# SEQ.net
KiCad netlist of a schematic drawn in EAGLE
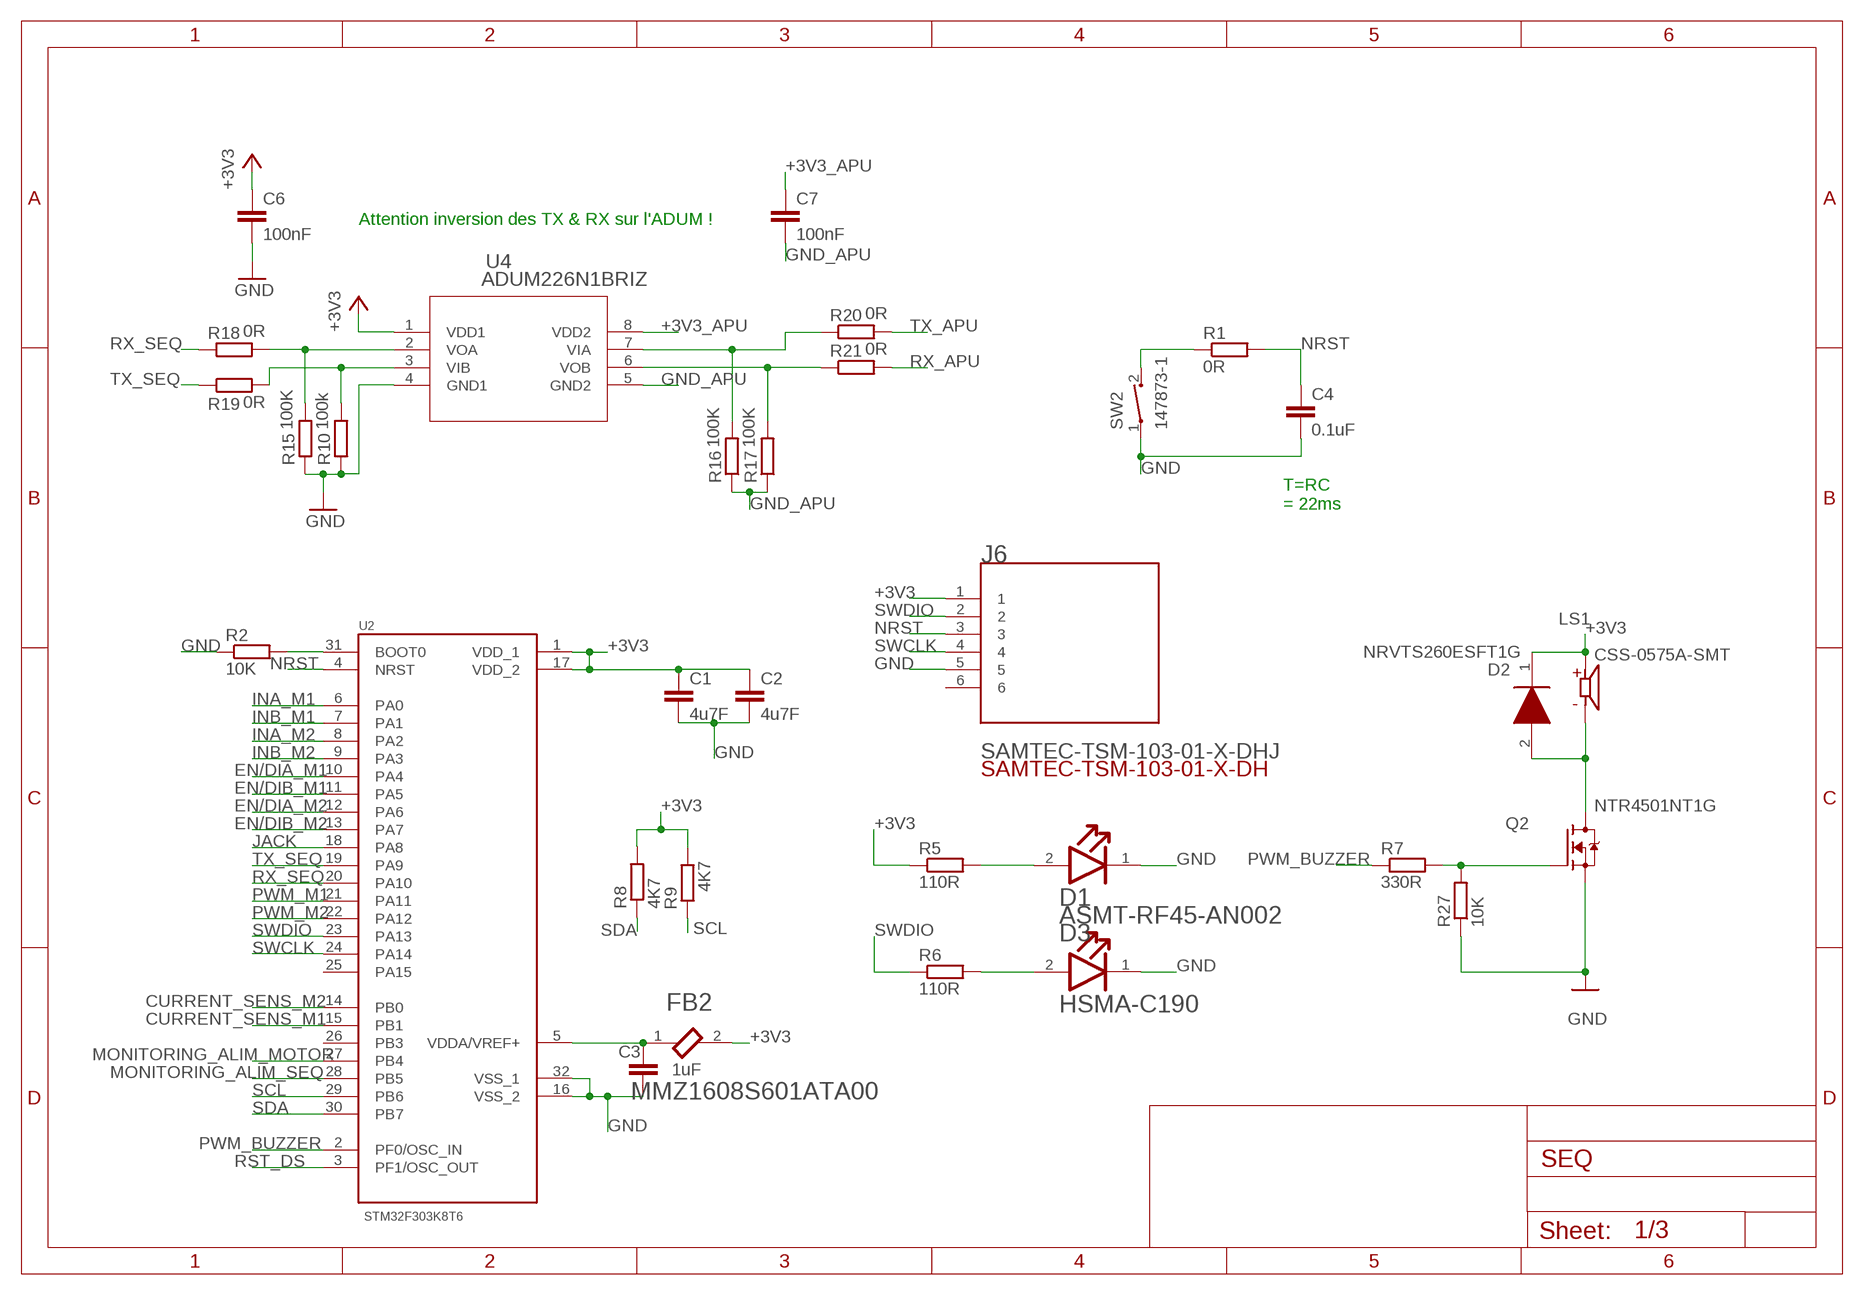
[diagram p0: schematic, sheet 1]
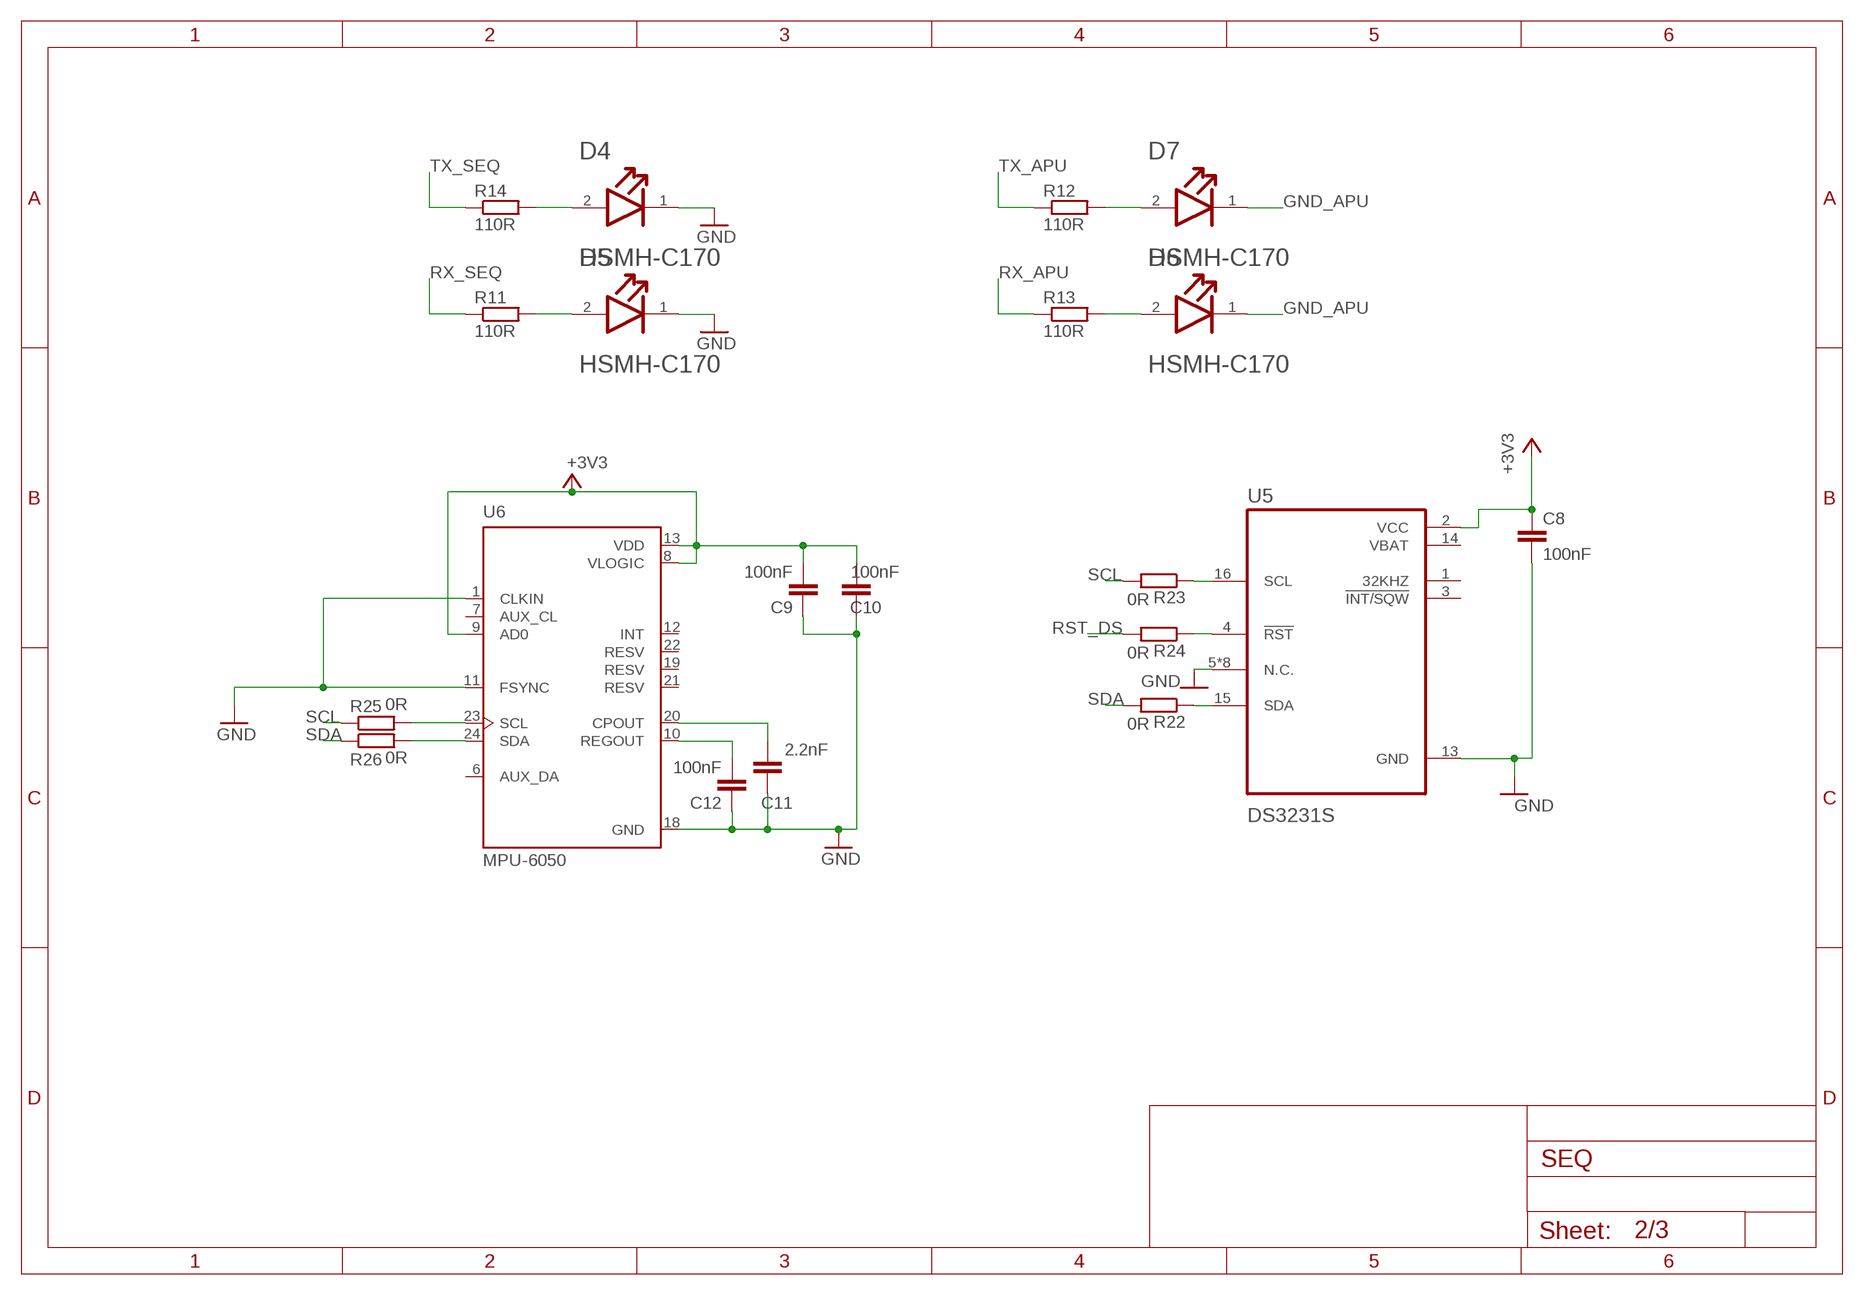
[diagram p1: schematic, sheet 2]
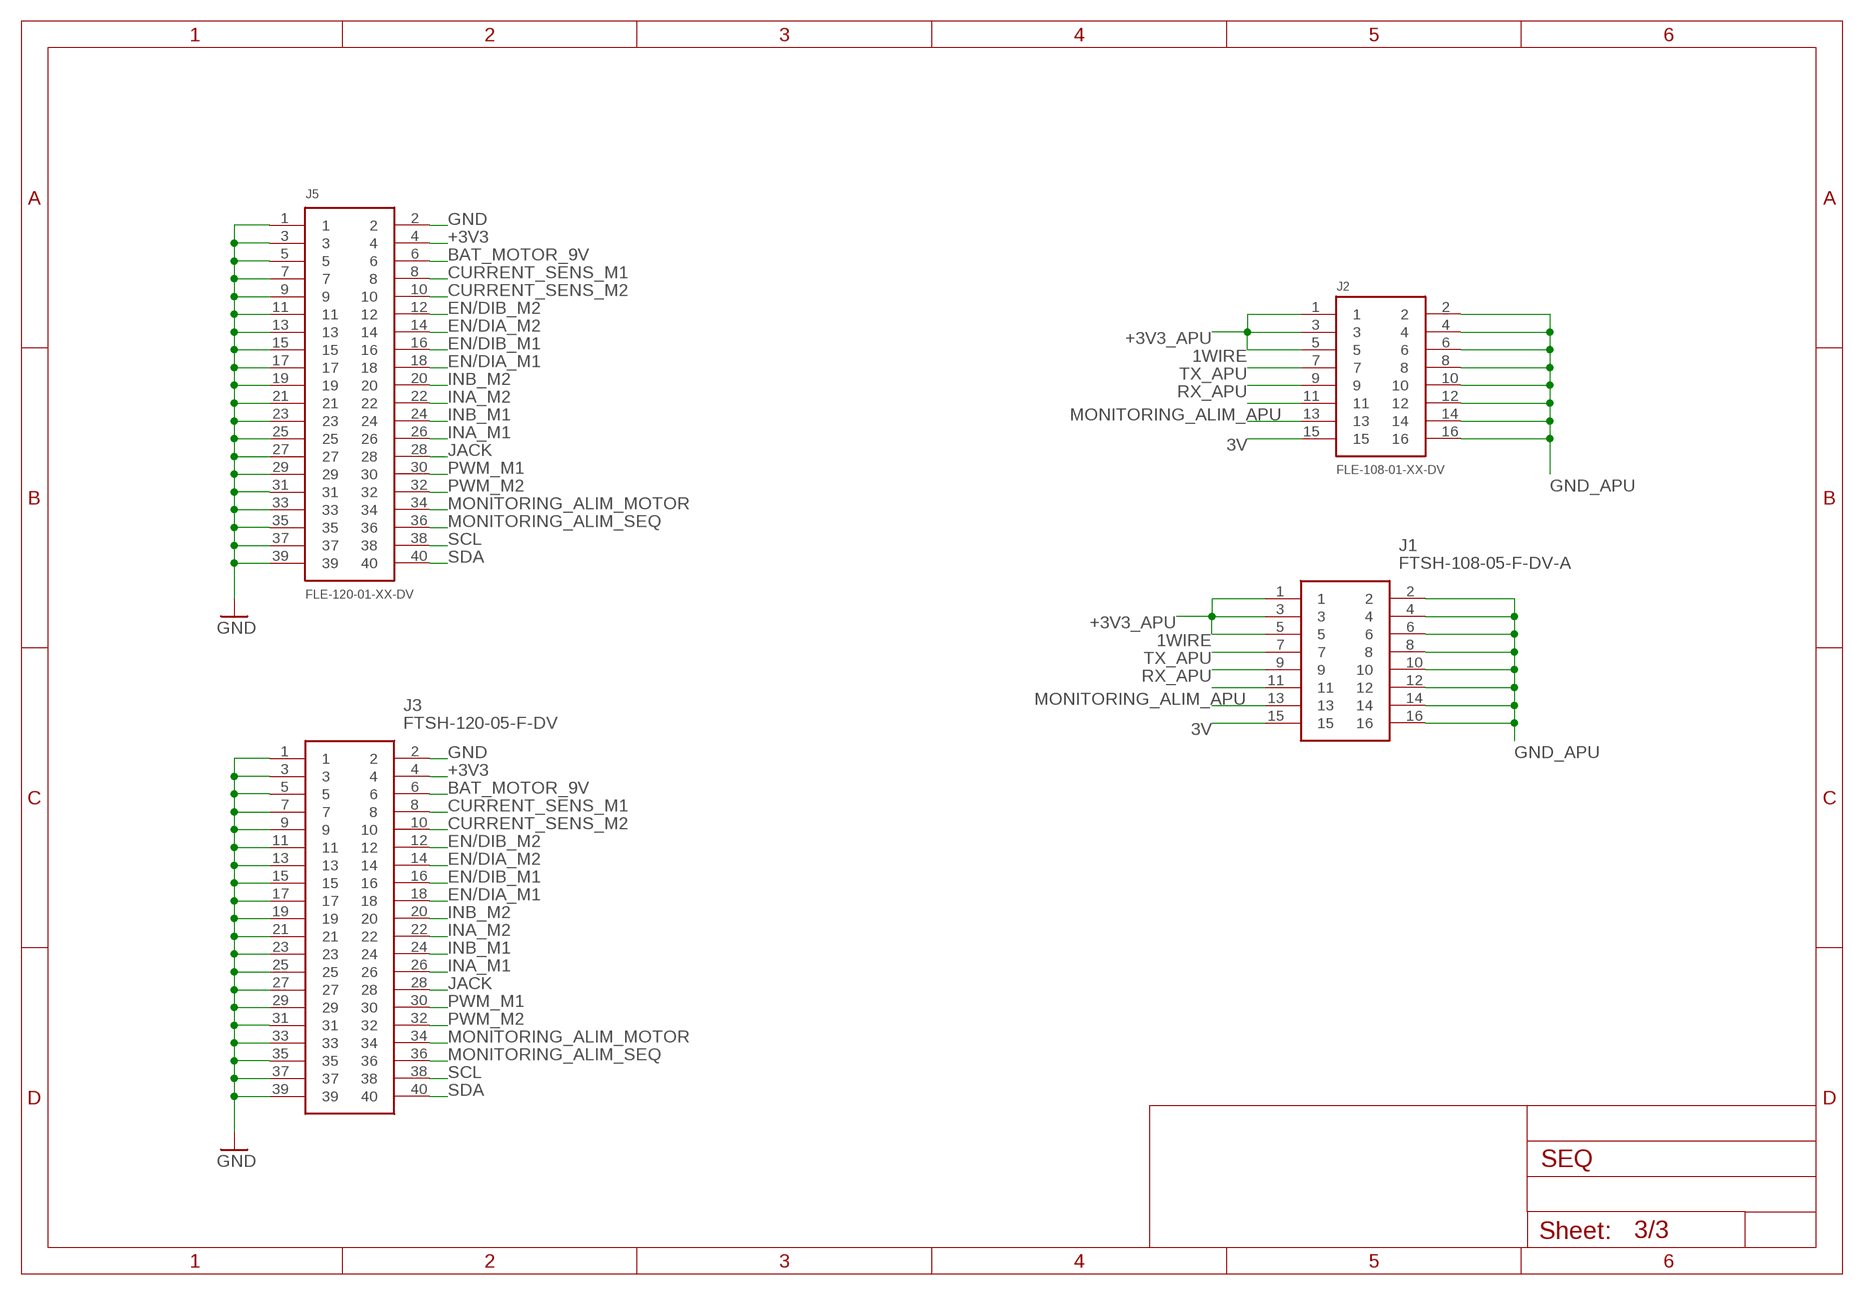
[diagram p2: schematic, sheet 3]

(export (version "E")
  (design (tool "Eeschema 10.0.6"))
  (components
    (comp (ref "C1")
      (value "4u7F")
      (footprint "eagle-import:C0805K")
      (libsource (lib "eagle-import") (part "C-EUC0805K"))
    )
    (comp (ref "C2")
      (value "4u7F")
      (footprint "eagle-import:C0805K")
      (libsource (lib "eagle-import") (part "C-EUC0805K"))
    )
    (comp (ref "C3")
      (value "1uF")
      (footprint "eagle-import:C0805K")
      (libsource (lib "eagle-import") (part "C-EUC0805K"))
    )
    (comp (ref "C4")
      (value "0.1uF")
      (footprint "eagle-import:C0805K")
      (libsource (lib "eagle-import") (part "C-EUC0805K"))
    )
    (comp (ref "C6")
      (value "100nF")
      (footprint "eagle-import:C0805")
      (libsource (lib "eagle-import") (part "C-EUC0805"))
    )
    (comp (ref "C7")
      (value "100nF")
      (footprint "eagle-import:C0805")
      (libsource (lib "eagle-import") (part "C-EUC0805"))
    )
    (comp (ref "D1")
      (value "BROADCOM_ASMT-RF45-AN002BROADCOM_ASMT-RF45-AN002_0_0")
      (footprint "eagle-import:BROADCOM_ASMT-RF45-AN002_0")
      (fields
        (field (name "DIGIKEY_PART_NUMBER") "516-2522-1-ND")
        (field (name "MF") "Broadcom")
        (field (name "MOUSER_PART_NUMBER") "630-ASMT-RF45-AN002")
      )
      (libsource (lib "eagle-import") (part "BROADCOM_ASMT-RF45-AN002BROADCOM_ASMT-RF45-AN002_0_0"))
    )
    (comp (ref "D2")
      (value "NRVTS260ESFT1G")
      (footprint "eagle-import:SODFL3616X98N")
      (fields (field (name "MOUSER_PART_NUMBER") "863-NRVTS260ESFT1G"))
      (libsource (lib "eagle-import") (part "NRVTS260ESFT1G"))
    )
    (comp (ref "D3")
      (value "BROADCOM_HSMA-C190BROADCOM_HSMA-C190_0_0")
      (footprint "eagle-import:BROADCOM_HSMA-C190_0")
      (fields
        (field (name "DIGIKEY_PART_NUMBER") "516-1423-1-ND")
        (field (name "MF") "Broadcom")
        (field (name "MOUSER_PART_NUMBER") "630-HSMA-C190")
      )
      (libsource (lib "eagle-import") (part "BROADCOM_HSMA-C190BROADCOM_HSMA-C190_0_0"))
    )
    (comp (ref "FB2")
      (value "TDK_MMZ1608S601ATA00TDK_MMZ1608S601ATA00_0_0")
      (footprint "eagle-import:TDK_MMZ1608S601ATA00_0")
      (fields
        (field (name "MF") "TDK")
        (field (name "MPN") "MMZ1608S601ATA00")
        (field (name "TOLERANCE") "25%")
      )
      (libsource (lib "eagle-import") (part "TDK_MMZ1608S601ATA00TDK_MMZ1608S601ATA00_0_0"))
    )
    (comp (ref "J6")
      (value "SAMTEC-TSM-103-01-X-DHJ")
      (footprint "eagle-import:SAMTEC-TSM-103-01-X-DH")
      (fields (field (name "MF") "Samtec Inc.") (field (name "MP") "TSM-103-01-F-DH"))
      (libsource (lib "eagle-import") (part "SAMTEC-TSM-103-01-X-DHJ"))
    )
    (comp (ref "LS1")
      (value "CSS-0575A-SMT")
      (footprint "eagle-import:CUI_CSS-0575A-SMT")
      (fields (field (name "MF") "CUI"))
      (libsource (lib "eagle-import") (part "CSS-0575A-SMT"))
    )
    (comp (ref "Q2")
      (value "NTR4501NT1G")
      (footprint "eagle-import:SOT95P237X111-3N")
      (fields (field (name "MF") "ON Semiconductor"))
      (libsource (lib "eagle-import") (part "NTR4501NT1G"))
    )
    (comp (ref "R1")
      (value "0R")
      (footprint "eagle-import:R0603")
      (libsource (lib "eagle-import") (part "R-EU_R0603"))
    )
    (comp (ref "R2")
      (value "10K")
      (footprint "eagle-import:R0603")
      (libsource (lib "eagle-import") (part "R-EU_R0603"))
    )
    (comp (ref "R5")
      (value "110R")
      (footprint "eagle-import:R0603")
      (libsource (lib "eagle-import") (part "R-EU_R0603"))
    )
    (comp (ref "R6")
      (value "110R")
      (footprint "eagle-import:R0603")
      (libsource (lib "eagle-import") (part "R-EU_R0603"))
    )
    (comp (ref "R7")
      (value "330R")
      (footprint "eagle-import:R0603")
      (libsource (lib "eagle-import") (part "R-EU_R0603"))
    )
    (comp (ref "R8")
      (value "4K7")
      (footprint "eagle-import:R0603")
      (libsource (lib "eagle-import") (part "R-EU_R0603"))
    )
    (comp (ref "R9")
      (value "4K7")
      (footprint "eagle-import:R0603")
      (libsource (lib "eagle-import") (part "R-EU_R0603"))
    )
    (comp (ref "R10")
      (value "100k")
      (footprint "eagle-import:R0603")
      (libsource (lib "eagle-import") (part "R-EU_R0603"))
    )
    (comp (ref "R15")
      (value "100K")
      (footprint "eagle-import:R0603")
      (libsource (lib "eagle-import") (part "R-EU_R0603"))
    )
    (comp (ref "R16")
      (value "100K")
      (footprint "eagle-import:R0603")
      (libsource (lib "eagle-import") (part "R-EU_R0603"))
    )
    (comp (ref "R17")
      (value "100K")
      (footprint "eagle-import:R0603")
      (libsource (lib "eagle-import") (part "R-EU_R0603"))
    )
    (comp (ref "R18")
      (value "0R")
      (footprint "eagle-import:R0603")
      (libsource (lib "eagle-import") (part "R-EU_R0603"))
    )
    (comp (ref "R19")
      (value "0R")
      (footprint "eagle-import:R0603")
      (libsource (lib "eagle-import") (part "R-EU_R0603"))
    )
    (comp (ref "R20")
      (value "0R")
      (footprint "eagle-import:R0603")
      (libsource (lib "eagle-import") (part "R-EU_R0603"))
    )
    (comp (ref "R21")
      (value "0R")
      (footprint "eagle-import:R0603")
      (libsource (lib "eagle-import") (part "R-EU_R0603"))
    )
    (comp (ref "R27")
      (value "10K")
      (footprint "eagle-import:R0603")
      (libsource (lib "eagle-import") (part "R-EU_R0603"))
    )
    (comp (ref "SW2")
      (value "147873-1")
      (footprint "eagle-import:SW_147873-1")
      (fields (field (name "MF") "TE Connectivity"))
      (libsource (lib "eagle-import") (part "147873-1"))
    )
    (comp (ref "U2")
      (value "STM32F303K8T6")
      (footprint "eagle-import:QFP80P900X900X160-32N")
      (fields (field (name "MANUFACTURER") "ST microelectronics"))
      (libsource (lib "eagle-import") (part "STM32F303K8T6"))
    )
    (comp (ref "U4")
      (value "ADUM226N1BRIZ")
      (footprint "eagle-import:RI_8_1_ADI")
      (libsource (lib "eagle-import") (part "ADUM226N1BRIZ"))
    )
    (comp (ref "J1")
      (value "FTSH-108-05-F-DV-A")
      (footprint "eagle-import:FTSH-108-XX-YYY-DV-A")
      (fields (field (name "MOUSER_PART_NUMBER") "200-FTSH10805FDVA"))
      (libsource (lib "eagle-import") (part "FTSH-108-05-F-DV-A"))
    )
    (comp (ref "J2")
      (value "FLE-108-01-XX-DV")
      (footprint "eagle-import:FLE-108-01-XX-DV")
      (fields (field (name "MF") "Samtec") (field (name "MP") "FLE-108-01-G-DV"))
      (libsource (lib "eagle-import") (part "FLE-108-01-XX-DV"))
    )
    (comp (ref "J3")
      (value "FTSH-120-05-F-DV")
      (footprint "eagle-import:FTSH-120-XX-YYY-DV")
      (libsource (lib "eagle-import") (part "FTSH-120-05-F-DV"))
    )
    (comp (ref "J5")
      (value "FLE-120-01-XX-DV")
      (footprint "eagle-import:FLE-120-01-XX-DV")
      (fields (field (name "MF") "Samtec") (field (name "MP") "FLE-120-01-G-DV"))
      (libsource (lib "eagle-import") (part "FLE-120-01-XX-DV"))
    )
    (comp (ref "C8")
      (value "100nF")
      (footprint "eagle-import:C0805")
      (libsource (lib "eagle-import") (part "C-EUC0805"))
    )
    (comp (ref "C9")
      (value "100nF")
      (footprint "eagle-import:C0805")
      (libsource (lib "eagle-import") (part "C-EUC0805"))
    )
    (comp (ref "C10")
      (value "100nF")
      (footprint "eagle-import:C0805")
      (libsource (lib "eagle-import") (part "C-EUC0805"))
    )
    (comp (ref "C11")
      (value "2.2nF")
      (footprint "eagle-import:C0805")
      (libsource (lib "eagle-import") (part "C-EUC0805"))
    )
    (comp (ref "C12")
      (value "100nF")
      (footprint "eagle-import:C0805")
      (libsource (lib "eagle-import") (part "C-EUC0805"))
    )
    (comp (ref "D4")
      (value "BROADCOM_HSMH-C170BROADCOM_HSMH-C170_0_0")
      (footprint "eagle-import:BROADCOM_HSMH-C170_0")
      (fields
        (field (name "DIGIKEY_PART_NUMBER") "516-1427-1-ND")
        (field (name "MF") "Broadcom")
        (field (name "MOUSER_PART_NUMBER") "630-HSMH-C170")
      )
      (libsource (lib "eagle-import") (part "BROADCOM_HSMH-C170BROADCOM_HSMH-C170_0_0"))
    )
    (comp (ref "D5")
      (value "BROADCOM_HSMH-C170BROADCOM_HSMH-C170_0_0")
      (footprint "eagle-import:BROADCOM_HSMH-C170_0")
      (fields
        (field (name "DIGIKEY_PART_NUMBER") "516-1427-1-ND")
        (field (name "MF") "Broadcom")
        (field (name "MOUSER_PART_NUMBER") "630-HSMH-C170")
      )
      (libsource (lib "eagle-import") (part "BROADCOM_HSMH-C170BROADCOM_HSMH-C170_0_0"))
    )
    (comp (ref "D6")
      (value "BROADCOM_HSMH-C170BROADCOM_HSMH-C170_0_0")
      (footprint "eagle-import:BROADCOM_HSMH-C170_0")
      (fields
        (field (name "DIGIKEY_PART_NUMBER") "516-1427-1-ND")
        (field (name "MF") "Broadcom")
        (field (name "MOUSER_PART_NUMBER") "630-HSMH-C170")
      )
      (libsource (lib "eagle-import") (part "BROADCOM_HSMH-C170BROADCOM_HSMH-C170_0_0"))
    )
    (comp (ref "D7")
      (value "BROADCOM_HSMH-C170BROADCOM_HSMH-C170_0_0")
      (footprint "eagle-import:BROADCOM_HSMH-C170_0")
      (fields
        (field (name "DIGIKEY_PART_NUMBER") "516-1427-1-ND")
        (field (name "MF") "Broadcom")
        (field (name "MOUSER_PART_NUMBER") "630-HSMH-C170")
      )
      (libsource (lib "eagle-import") (part "BROADCOM_HSMH-C170BROADCOM_HSMH-C170_0_0"))
    )
    (comp (ref "R11")
      (value "110R")
      (footprint "eagle-import:R0603")
      (libsource (lib "eagle-import") (part "R-EU_R0603"))
    )
    (comp (ref "R12")
      (value "110R")
      (footprint "eagle-import:R0603")
      (libsource (lib "eagle-import") (part "R-EU_R0603"))
    )
    (comp (ref "R13")
      (value "110R")
      (footprint "eagle-import:R0603")
      (libsource (lib "eagle-import") (part "R-EU_R0603"))
    )
    (comp (ref "R14")
      (value "110R")
      (footprint "eagle-import:R0603")
      (libsource (lib "eagle-import") (part "R-EU_R0603"))
    )
    (comp (ref "R22")
      (value "0R")
      (footprint "eagle-import:R0603")
      (libsource (lib "eagle-import") (part "R-EU_R0603"))
    )
    (comp (ref "R23")
      (value "0R")
      (footprint "eagle-import:R0603")
      (libsource (lib "eagle-import") (part "R-EU_R0603"))
    )
    (comp (ref "R24")
      (value "0R")
      (footprint "eagle-import:R0603")
      (libsource (lib "eagle-import") (part "R-EU_R0603"))
    )
    (comp (ref "R25")
      (value "0R")
      (footprint "eagle-import:R0603")
      (libsource (lib "eagle-import") (part "R-EU_R0603"))
    )
    (comp (ref "R26")
      (value "0R")
      (footprint "eagle-import:R0603")
      (libsource (lib "eagle-import") (part "R-EU_R0603"))
    )
    (comp (ref "U5")
      (value "DS3231S")
      (footprint "eagle-import:SOIC127P1032X265-16N")
      (fields (field (name "MF") "Maxim Integrated"))
      (libsource (lib "eagle-import") (part "DS3231S"))
    )
    (comp (ref "U6")
      (value "MPU-6050")
      (footprint "eagle-import:QFN50P400X400X95-24N")
      (fields (field (name "MF") "TDK InvenSense"))
      (libsource (lib "eagle-import") (part "MPU-6050"))
    )
  )
  (nets
    (net (code "1") (name "+3V3") (class "Default")
      (node (ref "C1") (pin "1") (pinfunction "1_1") (pintype "passive"))
      (node (ref "C10") (pin "2") (pinfunction "2_2") (pintype "passive"))
      (node (ref "C2") (pin "1") (pinfunction "1_1") (pintype "passive"))
      (node (ref "C6") (pin "1") (pinfunction "1_1") (pintype "passive"))
      (node (ref "C8") (pin "1") (pinfunction "1_1") (pintype "passive"))
      (node (ref "C9") (pin "2") (pinfunction "2_2") (pintype "passive"))
      (node (ref "D2") (pin "1") (pinfunction "K_1") (pintype "bidirectional"))
      (node (ref "FB2") (pin "2") (pinfunction "2_2") (pintype "passive"))
      (node (ref "J3") (pin "4") (pinfunction "4_4") (pintype "bidirectional"))
      (node (ref "J5") (pin "4") (pinfunction "4_4") (pintype "bidirectional"))
      (node (ref "J6") (pin "1") (pinfunction "1_1") (pintype "bidirectional"))
      (node (ref "LS1") (pin "1") (pinfunction "P_1") (pintype "passive"))
      (node (ref "R5") (pin "1") (pinfunction "1_1") (pintype "passive"))
      (node (ref "R8") (pin "2") (pinfunction "2_2") (pintype "passive"))
      (node (ref "R9") (pin "2") (pinfunction "2_2") (pintype "passive"))
      (node (ref "U2") (pin "1") (pinfunction "VDD_1_1") (pintype "power_in"))
      (node (ref "U2") (pin "17") (pinfunction "VDD_2_17") (pintype "power_in"))
      (node (ref "U4") (pin "1") (pinfunction "VDD1_1") (pintype "passive"))
      (node (ref "U5") (pin "2") (pinfunction "VCC_2") (pintype "power_in"))
      (node (ref "U6") (pin "13") (pinfunction "VDD_13") (pintype "power_in"))
      (node (ref "U6") (pin "8") (pinfunction "VLOGIC_8") (pintype "power_in"))
      (node (ref "U6") (pin "9") (pinfunction "AD0_9") (pintype "input"))
    )
    (net (code "2") (name "+3V3_APU") (class "Default")
      (node (ref "C7") (pin "1") (pinfunction "1_1") (pintype "passive"))
      (node (ref "J1") (pin "1") (pinfunction "1_1") (pintype "bidirectional"))
      (node (ref "J1") (pin "3") (pinfunction "3_3") (pintype "bidirectional"))
      (node (ref "J1") (pin "5") (pinfunction "5_5") (pintype "bidirectional"))
      (node (ref "J2") (pin "1") (pinfunction "1_1") (pintype "bidirectional"))
      (node (ref "J2") (pin "3") (pinfunction "3_3") (pintype "bidirectional"))
      (node (ref "J2") (pin "5") (pinfunction "5_5") (pintype "bidirectional"))
      (node (ref "U4") (pin "8") (pinfunction "VDD2_8") (pintype "passive"))
    )
    (net (code "3") (name "1WIRE") (class "Default")
      (node (ref "J1") (pin "7") (pinfunction "7_7") (pintype "bidirectional"))
      (node (ref "J2") (pin "7") (pinfunction "7_7") (pintype "bidirectional"))
    )
    (net (code "4") (name "3V") (class "Default")
      (node (ref "J1") (pin "15") (pinfunction "15_15") (pintype "bidirectional"))
      (node (ref "J2") (pin "15") (pinfunction "15_15") (pintype "bidirectional"))
    )
    (net (code "5") (name "BAT_MOTOR_9V") (class "Default")
      (node (ref "J3") (pin "6") (pinfunction "6_6") (pintype "bidirectional"))
      (node (ref "J5") (pin "6") (pinfunction "6_6") (pintype "bidirectional"))
    )
    (net (code "6") (name "CURRENT_SENS_M1") (class "Default")
      (node (ref "J3") (pin "8") (pinfunction "8_8") (pintype "bidirectional"))
      (node (ref "J5") (pin "8") (pinfunction "8_8") (pintype "bidirectional"))
      (node (ref "U2") (pin "15") (pinfunction "PB1_15") (pintype "bidirectional"))
    )
    (net (code "7") (name "CURRENT_SENS_M2") (class "Default")
      (node (ref "J3") (pin "10") (pinfunction "10_10") (pintype "bidirectional"))
      (node (ref "J5") (pin "10") (pinfunction "10_10") (pintype "bidirectional"))
      (node (ref "U2") (pin "14") (pinfunction "PB0_14") (pintype "bidirectional"))
    )
    (net (code "8") (name "EN{slash}DIA_M1") (class "Default")
      (node (ref "J3") (pin "18") (pinfunction "18_18") (pintype "bidirectional"))
      (node (ref "J5") (pin "18") (pinfunction "18_18") (pintype "bidirectional"))
      (node (ref "U2") (pin "10") (pinfunction "PA4_10") (pintype "bidirectional"))
    )
    (net (code "9") (name "EN{slash}DIA_M2") (class "Default")
      (node (ref "J3") (pin "14") (pinfunction "14_14") (pintype "bidirectional"))
      (node (ref "J5") (pin "14") (pinfunction "14_14") (pintype "bidirectional"))
      (node (ref "U2") (pin "12") (pinfunction "PA6_12") (pintype "bidirectional"))
    )
    (net (code "10") (name "EN{slash}DIB_M1") (class "Default")
      (node (ref "J3") (pin "16") (pinfunction "16_16") (pintype "bidirectional"))
      (node (ref "J5") (pin "16") (pinfunction "16_16") (pintype "bidirectional"))
      (node (ref "U2") (pin "11") (pinfunction "PA5_11") (pintype "bidirectional"))
    )
    (net (code "11") (name "EN{slash}DIB_M2") (class "Default")
      (node (ref "J3") (pin "12") (pinfunction "12_12") (pintype "bidirectional"))
      (node (ref "J5") (pin "12") (pinfunction "12_12") (pintype "bidirectional"))
      (node (ref "U2") (pin "13") (pinfunction "PA7_13") (pintype "bidirectional"))
    )
    (net (code "12") (name "GND") (class "Default")
      (node (ref "C1") (pin "2") (pinfunction "2_2") (pintype "passive"))
      (node (ref "C10") (pin "1") (pinfunction "1_1") (pintype "passive"))
      (node (ref "C11") (pin "1") (pinfunction "1_1") (pintype "passive"))
      (node (ref "C12") (pin "1") (pinfunction "1_1") (pintype "passive"))
      (node (ref "C2") (pin "2") (pinfunction "2_2") (pintype "passive"))
      (node (ref "C3") (pin "2") (pinfunction "2_2") (pintype "passive"))
      (node (ref "C4") (pin "2") (pinfunction "2_2") (pintype "passive"))
      (node (ref "C6") (pin "2") (pinfunction "2_2") (pintype "passive"))
      (node (ref "C8") (pin "2") (pinfunction "2_2") (pintype "passive"))
      (node (ref "C9") (pin "1") (pinfunction "1_1") (pintype "passive"))
      (node (ref "D1") (pin "1") (pinfunction "CATHODE_1") (pintype "passive"))
      (node (ref "D3") (pin "1") (pinfunction "CATHODE_1") (pintype "passive"))
      (node (ref "D4") (pin "1") (pinfunction "CATHODE_1") (pintype "passive"))
      (node (ref "D5") (pin "1") (pinfunction "CATHODE_1") (pintype "passive"))
      (node (ref "J3") (pin "1") (pinfunction "1_1") (pintype "bidirectional"))
      (node (ref "J3") (pin "11") (pinfunction "11_11") (pintype "bidirectional"))
      (node (ref "J3") (pin "13") (pinfunction "13_13") (pintype "bidirectional"))
      (node (ref "J3") (pin "15") (pinfunction "15_15") (pintype "bidirectional"))
      (node (ref "J3") (pin "17") (pinfunction "17_17") (pintype "bidirectional"))
      (node (ref "J3") (pin "19") (pinfunction "19_19") (pintype "bidirectional"))
      (node (ref "J3") (pin "2") (pinfunction "2_2") (pintype "bidirectional"))
      (node (ref "J3") (pin "21") (pinfunction "21_21") (pintype "bidirectional"))
      (node (ref "J3") (pin "23") (pinfunction "23_23") (pintype "bidirectional"))
      (node (ref "J3") (pin "25") (pinfunction "25_25") (pintype "bidirectional"))
      (node (ref "J3") (pin "27") (pinfunction "27_27") (pintype "bidirectional"))
      (node (ref "J3") (pin "29") (pinfunction "29_29") (pintype "bidirectional"))
      (node (ref "J3") (pin "3") (pinfunction "3_3") (pintype "bidirectional"))
      (node (ref "J3") (pin "31") (pinfunction "31_31") (pintype "bidirectional"))
      (node (ref "J3") (pin "33") (pinfunction "33_33") (pintype "bidirectional"))
      (node (ref "J3") (pin "35") (pinfunction "35_35") (pintype "bidirectional"))
      (node (ref "J3") (pin "37") (pinfunction "37_37") (pintype "bidirectional"))
      (node (ref "J3") (pin "39") (pinfunction "39_39") (pintype "bidirectional"))
      (node (ref "J3") (pin "5") (pinfunction "5_5") (pintype "bidirectional"))
      (node (ref "J3") (pin "7") (pinfunction "7_7") (pintype "bidirectional"))
      (node (ref "J3") (pin "9") (pinfunction "9_9") (pintype "bidirectional"))
      (node (ref "J5") (pin "1") (pinfunction "1_1") (pintype "bidirectional"))
      (node (ref "J5") (pin "11") (pinfunction "11_11") (pintype "bidirectional"))
      (node (ref "J5") (pin "13") (pinfunction "13_13") (pintype "bidirectional"))
      (node (ref "J5") (pin "15") (pinfunction "15_15") (pintype "bidirectional"))
      (node (ref "J5") (pin "17") (pinfunction "17_17") (pintype "bidirectional"))
      (node (ref "J5") (pin "19") (pinfunction "19_19") (pintype "bidirectional"))
      (node (ref "J5") (pin "2") (pinfunction "2_2") (pintype "bidirectional"))
      (node (ref "J5") (pin "21") (pinfunction "21_21") (pintype "bidirectional"))
      (node (ref "J5") (pin "23") (pinfunction "23_23") (pintype "bidirectional"))
      (node (ref "J5") (pin "25") (pinfunction "25_25") (pintype "bidirectional"))
      (node (ref "J5") (pin "27") (pinfunction "27_27") (pintype "bidirectional"))
      (node (ref "J5") (pin "29") (pinfunction "29_29") (pintype "bidirectional"))
      (node (ref "J5") (pin "3") (pinfunction "3_3") (pintype "bidirectional"))
      (node (ref "J5") (pin "31") (pinfunction "31_31") (pintype "bidirectional"))
      (node (ref "J5") (pin "33") (pinfunction "33_33") (pintype "bidirectional"))
      (node (ref "J5") (pin "35") (pinfunction "35_35") (pintype "bidirectional"))
      (node (ref "J5") (pin "37") (pinfunction "37_37") (pintype "bidirectional"))
      (node (ref "J5") (pin "39") (pinfunction "39_39") (pintype "bidirectional"))
      (node (ref "J5") (pin "5") (pinfunction "5_5") (pintype "bidirectional"))
      (node (ref "J5") (pin "7") (pinfunction "7_7") (pintype "bidirectional"))
      (node (ref "J5") (pin "9") (pinfunction "9_9") (pintype "bidirectional"))
      (node (ref "J6") (pin "5") (pinfunction "5_5") (pintype "bidirectional"))
      (node (ref "Q2") (pin "2") (pinfunction "S_2") (pintype "passive"))
      (node (ref "R10") (pin "1") (pinfunction "1_1") (pintype "passive"))
      (node (ref "R15") (pin "1") (pinfunction "1_1") (pintype "passive"))
      (node (ref "R2") (pin "1") (pinfunction "1_1") (pintype "passive"))
      (node (ref "R27") (pin "1") (pinfunction "1_1") (pintype "passive"))
      (node (ref "SW2") (pin "1") (pinfunction "1_1") (pintype "passive"))
      (node (ref "U2") (pin "16") (pinfunction "VSS_2_16") (pintype "power_in"))
      (node (ref "U2") (pin "32") (pinfunction "VSS_1_32") (pintype "power_in"))
      (node (ref "U4") (pin "4") (pinfunction "GND1_4") (pintype "passive"))
      (node (ref "U5") (pin "10") (pinfunction "N.C._10") (pintype "bidirectional"))
      (node (ref "U5") (pin "11") (pinfunction "N.C._11") (pintype "bidirectional"))
      (node (ref "U5") (pin "12") (pinfunction "N.C._12") (pintype "bidirectional"))
      (node (ref "U5") (pin "13") (pinfunction "GND_13") (pintype "power_in"))
      (node (ref "U5") (pin "5") (pinfunction "N.C._5") (pintype "bidirectional"))
      (node (ref "U5") (pin "6") (pinfunction "N.C._6") (pintype "bidirectional"))
      (node (ref "U5") (pin "7") (pinfunction "N.C._7") (pintype "bidirectional"))
      (node (ref "U5") (pin "8") (pinfunction "N.C._8") (pintype "bidirectional"))
      (node (ref "U5") (pin "9") (pinfunction "N.C._9") (pintype "bidirectional"))
      (node (ref "U6") (pin "1") (pinfunction "CLKIN_1") (pintype "input"))
      (node (ref "U6") (pin "11") (pinfunction "FSYNC_11") (pintype "input"))
      (node (ref "U6") (pin "18") (pinfunction "GND_18") (pintype "power_in"))
    )
    (net (code "13") (name "GND_APU") (class "Default")
      (node (ref "C7") (pin "2") (pinfunction "2_2") (pintype "passive"))
      (node (ref "D6") (pin "1") (pinfunction "CATHODE_1") (pintype "passive"))
      (node (ref "D7") (pin "1") (pinfunction "CATHODE_1") (pintype "passive"))
      (node (ref "J1") (pin "10") (pinfunction "10_10") (pintype "bidirectional"))
      (node (ref "J1") (pin "12") (pinfunction "12_12") (pintype "bidirectional"))
      (node (ref "J1") (pin "14") (pinfunction "14_14") (pintype "bidirectional"))
      (node (ref "J1") (pin "16") (pinfunction "16_16") (pintype "bidirectional"))
      (node (ref "J1") (pin "2") (pinfunction "2_2") (pintype "bidirectional"))
      (node (ref "J1") (pin "4") (pinfunction "4_4") (pintype "bidirectional"))
      (node (ref "J1") (pin "6") (pinfunction "6_6") (pintype "bidirectional"))
      (node (ref "J1") (pin "8") (pinfunction "8_8") (pintype "bidirectional"))
      (node (ref "J2") (pin "10") (pinfunction "10_10") (pintype "bidirectional"))
      (node (ref "J2") (pin "12") (pinfunction "12_12") (pintype "bidirectional"))
      (node (ref "J2") (pin "14") (pinfunction "14_14") (pintype "bidirectional"))
      (node (ref "J2") (pin "16") (pinfunction "16_16") (pintype "bidirectional"))
      (node (ref "J2") (pin "2") (pinfunction "2_2") (pintype "bidirectional"))
      (node (ref "J2") (pin "4") (pinfunction "4_4") (pintype "bidirectional"))
      (node (ref "J2") (pin "6") (pinfunction "6_6") (pintype "bidirectional"))
      (node (ref "J2") (pin "8") (pinfunction "8_8") (pintype "bidirectional"))
      (node (ref "R16") (pin "1") (pinfunction "1_1") (pintype "passive"))
      (node (ref "R17") (pin "1") (pinfunction "1_1") (pintype "passive"))
      (node (ref "U4") (pin "5") (pinfunction "GND2_5") (pintype "passive"))
    )
    (net (code "14") (name "INA_M1") (class "Default")
      (node (ref "J3") (pin "26") (pinfunction "26_26") (pintype "bidirectional"))
      (node (ref "J5") (pin "26") (pinfunction "26_26") (pintype "bidirectional"))
      (node (ref "U2") (pin "6") (pinfunction "PA0_6") (pintype "bidirectional"))
    )
    (net (code "15") (name "INA_M2") (class "Default")
      (node (ref "J3") (pin "22") (pinfunction "22_22") (pintype "bidirectional"))
      (node (ref "J5") (pin "22") (pinfunction "22_22") (pintype "bidirectional"))
      (node (ref "U2") (pin "8") (pinfunction "PA2_8") (pintype "bidirectional"))
    )
    (net (code "16") (name "INB_M1") (class "Default")
      (node (ref "J3") (pin "24") (pinfunction "24_24") (pintype "bidirectional"))
      (node (ref "J5") (pin "24") (pinfunction "24_24") (pintype "bidirectional"))
      (node (ref "U2") (pin "7") (pinfunction "PA1_7") (pintype "bidirectional"))
    )
    (net (code "17") (name "INB_M2") (class "Default")
      (node (ref "J3") (pin "20") (pinfunction "20_20") (pintype "bidirectional"))
      (node (ref "J5") (pin "20") (pinfunction "20_20") (pintype "bidirectional"))
      (node (ref "U2") (pin "9") (pinfunction "PA3_9") (pintype "bidirectional"))
    )
    (net (code "18") (name "JACK") (class "Default")
      (node (ref "J3") (pin "28") (pinfunction "28_28") (pintype "bidirectional"))
      (node (ref "J5") (pin "28") (pinfunction "28_28") (pintype "bidirectional"))
      (node (ref "U2") (pin "18") (pinfunction "PA8_18") (pintype "bidirectional"))
    )
    (net (code "19") (name "MONITORING_ALIM_APU") (class "Default")
      (node (ref "J1") (pin "13") (pinfunction "13_13") (pintype "bidirectional"))
      (node (ref "J2") (pin "13") (pinfunction "13_13") (pintype "bidirectional"))
    )
    (net (code "20") (name "MONITORING_ALIM_MOTOR") (class "Default")
      (node (ref "J3") (pin "34") (pinfunction "34_34") (pintype "bidirectional"))
      (node (ref "J5") (pin "34") (pinfunction "34_34") (pintype "bidirectional"))
      (node (ref "U2") (pin "27") (pinfunction "PB4_27") (pintype "bidirectional"))
    )
    (net (code "21") (name "MONITORING_ALIM_SEQ") (class "Default")
      (node (ref "J3") (pin "36") (pinfunction "36_36") (pintype "bidirectional"))
      (node (ref "J5") (pin "36") (pinfunction "36_36") (pintype "bidirectional"))
      (node (ref "U2") (pin "28") (pinfunction "PB5_28") (pintype "bidirectional"))
    )
    (net (code "22") (name "NRST") (class "Default")
      (node (ref "C4") (pin "1") (pinfunction "1_1") (pintype "passive"))
      (node (ref "J6") (pin "3") (pinfunction "3_3") (pintype "bidirectional"))
      (node (ref "R1") (pin "2") (pinfunction "2_2") (pintype "passive"))
      (node (ref "U2") (pin "4") (pinfunction "NRST_4") (pintype "bidirectional"))
    )
    (net (code "23") (name "Net-(D1-ANODE)") (class "Default")
      (node (ref "D1") (pin "2") (pinfunction "ANODE_2") (pintype "passive"))
      (node (ref "R5") (pin "2") (pinfunction "2_2") (pintype "passive"))
    )
    (net (code "24") (name "Net-(D2-A)") (class "Default")
      (node (ref "D2") (pin "2") (pinfunction "A_2") (pintype "bidirectional"))
      (node (ref "LS1") (pin "2") (pinfunction "N_2") (pintype "passive"))
      (node (ref "Q2") (pin "3") (pinfunction "D_3") (pintype "passive"))
    )
    (net (code "25") (name "Net-(D3-ANODE)") (class "Default")
      (node (ref "D3") (pin "2") (pinfunction "ANODE_2") (pintype "passive"))
      (node (ref "R6") (pin "2") (pinfunction "2_2") (pintype "passive"))
    )
    (net (code "26") (name "Net-(D4-ANODE)") (class "Default")
      (node (ref "D4") (pin "2") (pinfunction "ANODE_2") (pintype "passive"))
      (node (ref "R14") (pin "2") (pinfunction "2_2") (pintype "passive"))
    )
    (net (code "27") (name "Net-(D5-ANODE)") (class "Default")
      (node (ref "D5") (pin "2") (pinfunction "ANODE_2") (pintype "passive"))
      (node (ref "R11") (pin "2") (pinfunction "2_2") (pintype "passive"))
    )
    (net (code "28") (name "Net-(D6-ANODE)") (class "Default")
      (node (ref "D6") (pin "2") (pinfunction "ANODE_2") (pintype "passive"))
      (node (ref "R13") (pin "2") (pinfunction "2_2") (pintype "passive"))
    )
    (net (code "29") (name "Net-(D7-ANODE)") (class "Default")
      (node (ref "D7") (pin "2") (pinfunction "ANODE_2") (pintype "passive"))
      (node (ref "R12") (pin "2") (pinfunction "2_2") (pintype "passive"))
    )
    (net (code "30") (name "Net-(Q2-G)") (class "Default")
      (node (ref "Q2") (pin "1") (pinfunction "G_1") (pintype "passive"))
      (node (ref "R27") (pin "2") (pinfunction "2_2") (pintype "passive"))
      (node (ref "R7") (pin "2") (pinfunction "2_2") (pintype "passive"))
    )
    (net (code "31") (name "Net-(R1-Pad1)") (class "Default")
      (node (ref "R1") (pin "1") (pinfunction "1_1") (pintype "passive"))
      (node (ref "SW2") (pin "2") (pinfunction "2_2") (pintype "passive"))
    )
    (net (code "32") (name "Net-(U2-BOOT0)") (class "Default")
      (node (ref "R2") (pin "2") (pinfunction "2_2") (pintype "passive"))
      (node (ref "U2") (pin "31") (pinfunction "BOOT0_31") (pintype "input"))
    )
    (net (code "33") (name "Net-(U2-VDDA{slash}VREF+)") (class "Default")
      (node (ref "C3") (pin "1") (pinfunction "1_1") (pintype "passive"))
      (node (ref "FB2") (pin "1") (pinfunction "1_1") (pintype "passive"))
      (node (ref "U2") (pin "5") (pinfunction "VDDA/VREF+_5") (pintype "power_in"))
    )
    (net (code "34") (name "Net-(U4-VIA)") (class "Default")
      (node (ref "R16") (pin "2") (pinfunction "2_2") (pintype "passive"))
      (node (ref "R20") (pin "1") (pinfunction "1_1") (pintype "passive"))
      (node (ref "U4") (pin "7") (pinfunction "VIA_7") (pintype "passive"))
    )
    (net (code "35") (name "Net-(U4-VIB)") (class "Default")
      (node (ref "R10") (pin "2") (pinfunction "2_2") (pintype "passive"))
      (node (ref "R19") (pin "2") (pinfunction "2_2") (pintype "passive"))
      (node (ref "U4") (pin "3") (pinfunction "VIB_3") (pintype "passive"))
    )
    (net (code "36") (name "Net-(U4-VOA)") (class "Default")
      (node (ref "R15") (pin "2") (pinfunction "2_2") (pintype "passive"))
      (node (ref "R18") (pin "2") (pinfunction "2_2") (pintype "passive"))
      (node (ref "U4") (pin "2") (pinfunction "VOA_2") (pintype "passive"))
    )
    (net (code "37") (name "Net-(U4-VOB)") (class "Default")
      (node (ref "R17") (pin "2") (pinfunction "2_2") (pintype "passive"))
      (node (ref "R21") (pin "1") (pinfunction "1_1") (pintype "passive"))
      (node (ref "U4") (pin "6") (pinfunction "VOB_6") (pintype "passive"))
    )
    (net (code "38") (name "Net-(U5-SCL)") (class "Default")
      (node (ref "R23") (pin "1") (pinfunction "1_1") (pintype "passive"))
      (node (ref "U5") (pin "16") (pinfunction "SCL_16") (pintype "input"))
    )
    (net (code "39") (name "Net-(U5-SDA)") (class "Default")
      (node (ref "R22") (pin "1") (pinfunction "1_1") (pintype "passive"))
      (node (ref "U5") (pin "15") (pinfunction "SDA_15") (pintype "bidirectional"))
    )
    (net (code "40") (name "Net-(U5-~{RST})") (class "Default")
      (node (ref "R24") (pin "1") (pinfunction "1_1") (pintype "passive"))
      (node (ref "U5") (pin "4") (pinfunction "~{RST}_4") (pintype "bidirectional"))
    )
    (net (code "41") (name "Net-(U6-CPOUT)") (class "Default")
      (node (ref "C11") (pin "2") (pinfunction "2_2") (pintype "passive"))
      (node (ref "U6") (pin "20") (pinfunction "CPOUT_20") (pintype "passive"))
    )
    (net (code "42") (name "Net-(U6-REGOUT)") (class "Default")
      (node (ref "C12") (pin "2") (pinfunction "2_2") (pintype "passive"))
      (node (ref "U6") (pin "10") (pinfunction "REGOUT_10") (pintype "passive"))
    )
    (net (code "43") (name "Net-(U6-SCL)") (class "Default")
      (node (ref "R25") (pin "2") (pinfunction "2_2") (pintype "passive"))
      (node (ref "U6") (pin "23") (pinfunction "SCL_23") (pintype "input"))
    )
    (net (code "44") (name "Net-(U6-SDA)") (class "Default")
      (node (ref "R26") (pin "2") (pinfunction "2_2") (pintype "passive"))
      (node (ref "U6") (pin "24") (pinfunction "SDA_24") (pintype "bidirectional"))
    )
    (net (code "45") (name "PWM_BUZZER") (class "Default")
      (node (ref "R7") (pin "1") (pinfunction "1_1") (pintype "passive"))
      (node (ref "U2") (pin "2") (pinfunction "PF0/OSC_IN_2") (pintype "bidirectional"))
    )
    (net (code "46") (name "PWM_M1") (class "Default")
      (node (ref "J3") (pin "30") (pinfunction "30_30") (pintype "bidirectional"))
      (node (ref "J5") (pin "30") (pinfunction "30_30") (pintype "bidirectional"))
      (node (ref "U2") (pin "21") (pinfunction "PA11_21") (pintype "bidirectional"))
    )
    (net (code "47") (name "PWM_M2") (class "Default")
      (node (ref "J3") (pin "32") (pinfunction "32_32") (pintype "bidirectional"))
      (node (ref "J5") (pin "32") (pinfunction "32_32") (pintype "bidirectional"))
      (node (ref "U2") (pin "22") (pinfunction "PA12_22") (pintype "bidirectional"))
    )
    (net (code "48") (name "RST_DS") (class "Default")
      (node (ref "R24") (pin "2") (pinfunction "2_2") (pintype "passive"))
      (node (ref "U2") (pin "3") (pinfunction "PF1/OSC_OUT_3") (pintype "bidirectional"))
    )
    (net (code "49") (name "RX_APU") (class "Default")
      (node (ref "J1") (pin "11") (pinfunction "11_11") (pintype "bidirectional"))
      (node (ref "J2") (pin "11") (pinfunction "11_11") (pintype "bidirectional"))
      (node (ref "R13") (pin "1") (pinfunction "1_1") (pintype "passive"))
      (node (ref "R21") (pin "2") (pinfunction "2_2") (pintype "passive"))
    )
    (net (code "50") (name "RX_SEQ") (class "Default")
      (node (ref "R11") (pin "1") (pinfunction "1_1") (pintype "passive"))
      (node (ref "R18") (pin "1") (pinfunction "1_1") (pintype "passive"))
      (node (ref "U2") (pin "20") (pinfunction "PA10_20") (pintype "bidirectional"))
    )
    (net (code "51") (name "SCL") (class "Default")
      (node (ref "J3") (pin "38") (pinfunction "38_38") (pintype "bidirectional"))
      (node (ref "J5") (pin "38") (pinfunction "38_38") (pintype "bidirectional"))
      (node (ref "R23") (pin "2") (pinfunction "2_2") (pintype "passive"))
      (node (ref "R25") (pin "1") (pinfunction "1_1") (pintype "passive"))
      (node (ref "R9") (pin "1") (pinfunction "1_1") (pintype "passive"))
      (node (ref "U2") (pin "29") (pinfunction "PB6_29") (pintype "bidirectional"))
    )
    (net (code "52") (name "SDA") (class "Default")
      (node (ref "J3") (pin "40") (pinfunction "40_40") (pintype "bidirectional"))
      (node (ref "J5") (pin "40") (pinfunction "40_40") (pintype "bidirectional"))
      (node (ref "R22") (pin "2") (pinfunction "2_2") (pintype "passive"))
      (node (ref "R26") (pin "1") (pinfunction "1_1") (pintype "passive"))
      (node (ref "R8") (pin "1") (pinfunction "1_1") (pintype "passive"))
      (node (ref "U2") (pin "30") (pinfunction "PB7_30") (pintype "bidirectional"))
    )
    (net (code "53") (name "SWCLK") (class "Default")
      (node (ref "J6") (pin "4") (pinfunction "4_4") (pintype "bidirectional"))
      (node (ref "U2") (pin "24") (pinfunction "PA14_24") (pintype "bidirectional"))
    )
    (net (code "54") (name "SWDIO") (class "Default")
      (node (ref "J6") (pin "2") (pinfunction "2_2") (pintype "bidirectional"))
      (node (ref "R6") (pin "1") (pinfunction "1_1") (pintype "passive"))
      (node (ref "U2") (pin "23") (pinfunction "PA13_23") (pintype "bidirectional"))
    )
    (net (code "55") (name "TX_APU") (class "Default")
      (node (ref "J1") (pin "9") (pinfunction "9_9") (pintype "bidirectional"))
      (node (ref "J2") (pin "9") (pinfunction "9_9") (pintype "bidirectional"))
      (node (ref "R12") (pin "1") (pinfunction "1_1") (pintype "passive"))
      (node (ref "R20") (pin "2") (pinfunction "2_2") (pintype "passive"))
    )
    (net (code "56") (name "TX_SEQ") (class "Default")
      (node (ref "R14") (pin "1") (pinfunction "1_1") (pintype "passive"))
      (node (ref "R19") (pin "1") (pinfunction "1_1") (pintype "passive"))
      (node (ref "U2") (pin "19") (pinfunction "PA9_19") (pintype "bidirectional"))
    )
    (net (code "57") (name "VBAT") (class "Default")
      (node (ref "U5") (pin "14") (pinfunction "VBAT_14") (pintype "power_in"))
    )
    (net (code "58") (name "unconnected-(J6-Pad6)") (class "Default")
      (node (ref "J6") (pin "6") (pinfunction "6_6") (pintype "bidirectional"))
    )
    (net (code "59") (name "unconnected-(U2-PA15-Pad25)") (class "Default")
      (node (ref "U2") (pin "25") (pinfunction "PA15_25") (pintype "bidirectional"))
    )
    (net (code "60") (name "unconnected-(U2-PB3-Pad26)") (class "Default")
      (node (ref "U2") (pin "26") (pinfunction "PB3_26") (pintype "bidirectional"))
    )
    (net (code "61") (name "unconnected-(U5-32KHZ-Pad1)") (class "Default")
      (node (ref "U5") (pin "1") (pinfunction "32KHZ_1") (pintype "output"))
    )
    (net (code "62") (name "unconnected-(U5-~{INT{slash}SQW}-Pad3)") (class "Default")
      (node (ref "U5") (pin "3") (pinfunction "~{INT/SQW}_3") (pintype "output"))
    )
    (net (code "63") (name "unconnected-(U6-AUX_CL-Pad7)") (class "Default")
      (node (ref "U6") (pin "7") (pinfunction "AUX_CL_7") (pintype "input"))
    )
    (net (code "64") (name "unconnected-(U6-AUX_DA-Pad6)") (class "Default")
      (node (ref "U6") (pin "6") (pinfunction "AUX_DA_6") (pintype "bidirectional"))
    )
    (net (code "65") (name "unconnected-(U6-INT-Pad12)") (class "Default")
      (node (ref "U6") (pin "12") (pinfunction "INT_12") (pintype "output"))
    )
    (net (code "66") (name "unconnected-(U6-RESV-Pad19)") (class "Default")
      (node (ref "U6") (pin "19") (pinfunction "RESV_19") (pintype "passive"))
    )
    (net (code "67") (name "unconnected-(U6-RESV-Pad21)") (class "Default")
      (node (ref "U6") (pin "21") (pinfunction "RESV_21") (pintype "passive"))
    )
    (net (code "68") (name "unconnected-(U6-RESV-Pad22)") (class "Default")
      (node (ref "U6") (pin "22") (pinfunction "RESV_22") (pintype "passive"))
    )
  )
)
